# photon_v1_0_0.net
KiCad netlist of a schematic drawn in EAGLE
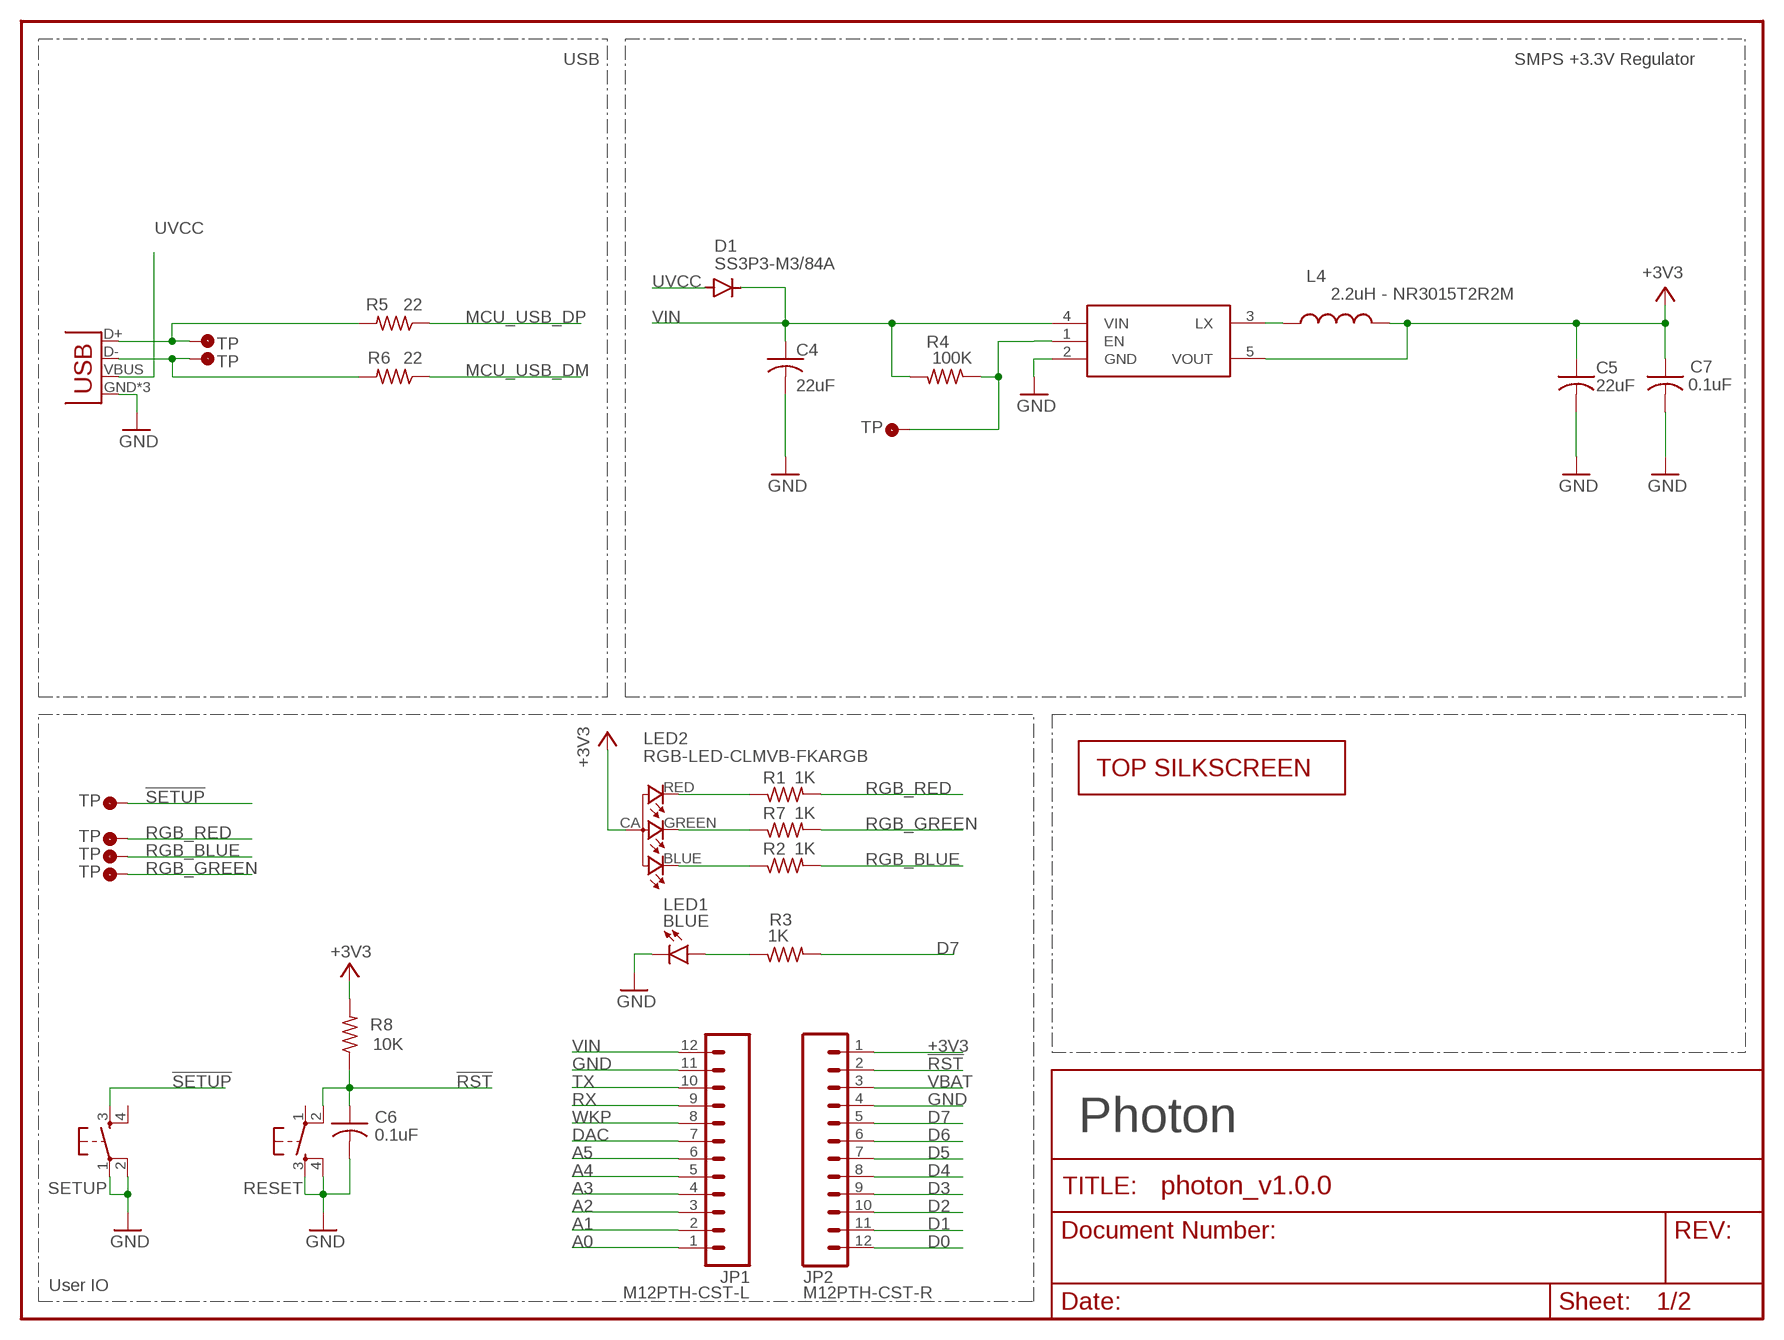
[diagram p0: schematic, sheet 1]
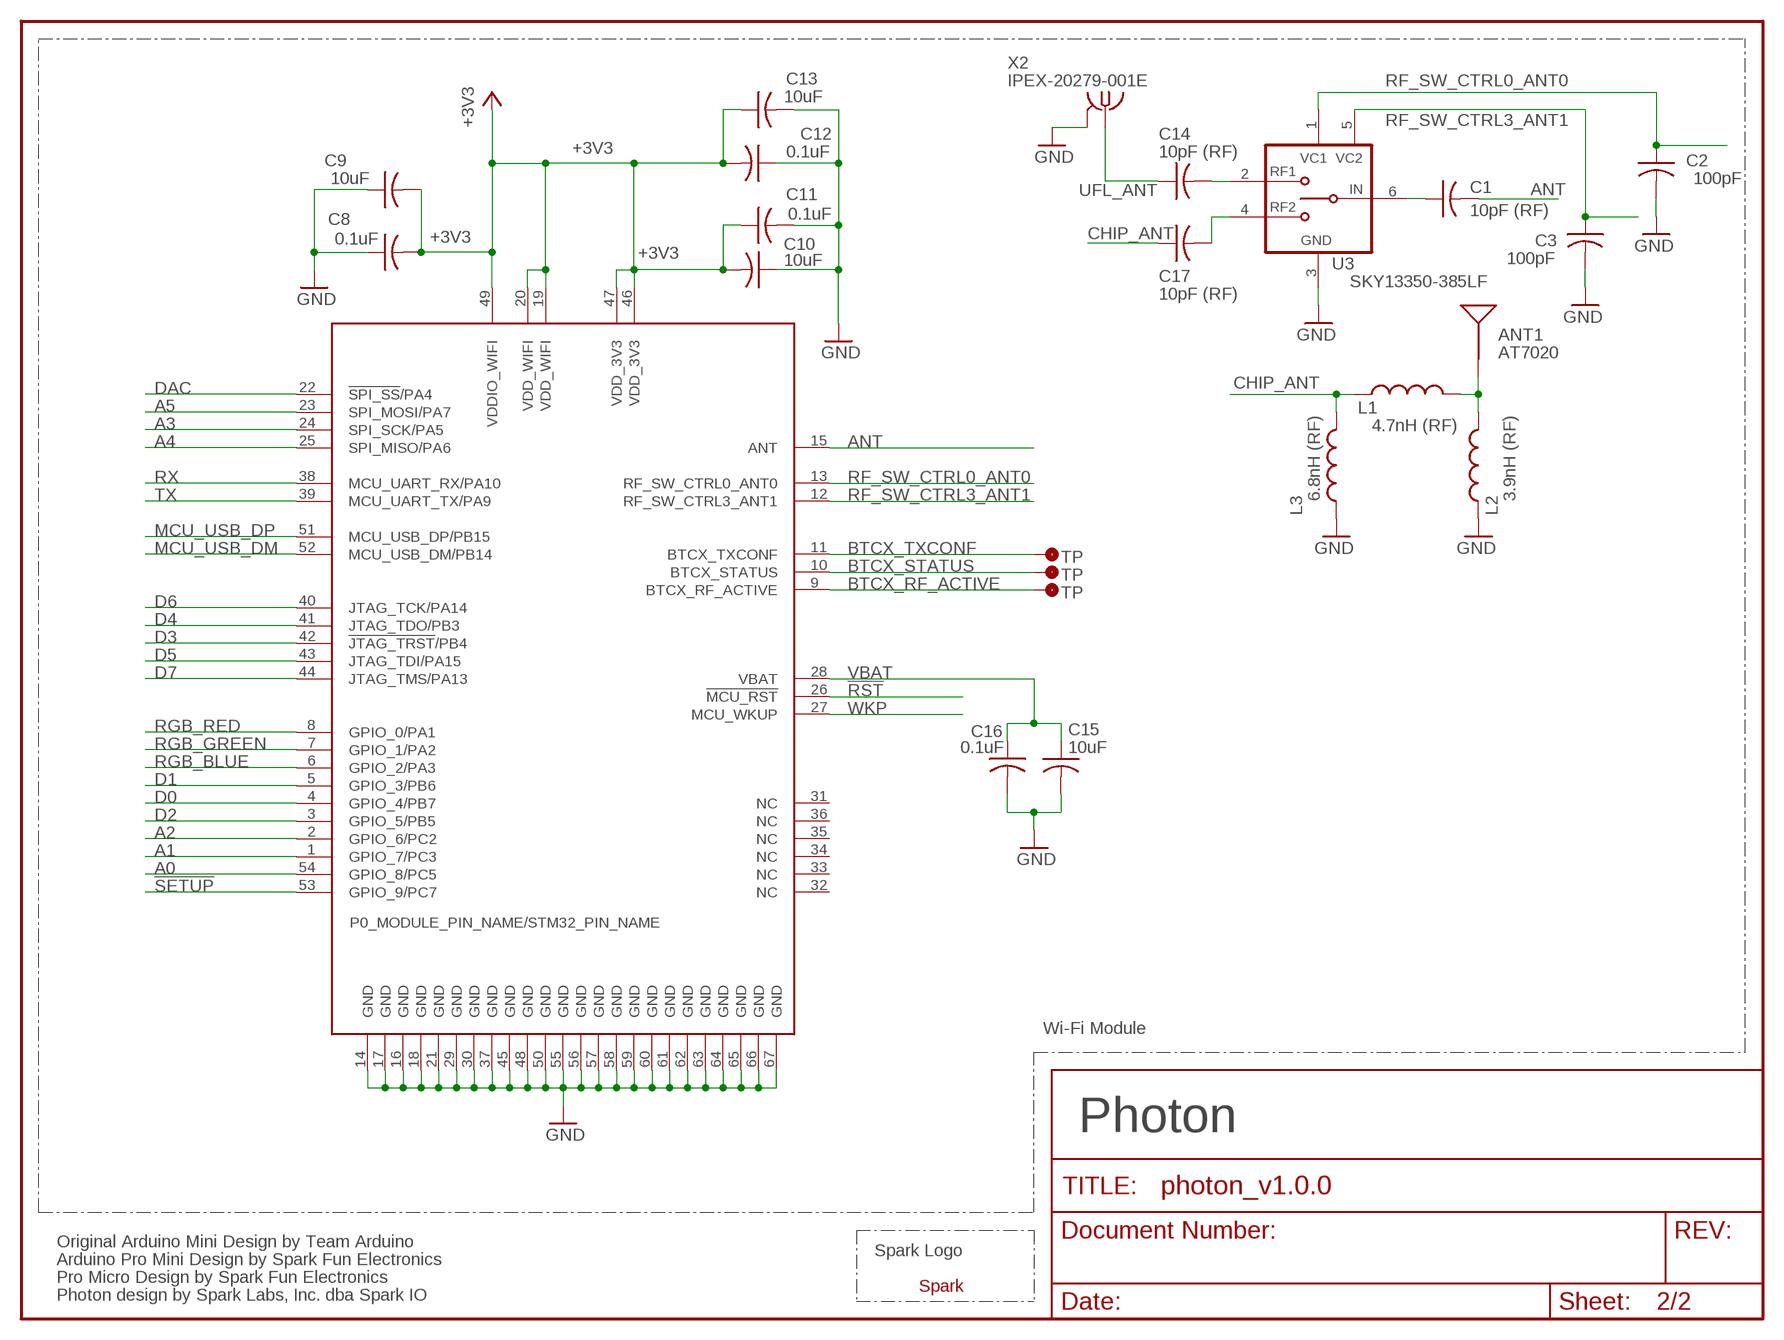
[diagram p1: schematic, sheet 2]

(export (version "E")
  (design (tool "Eeschema 10.0.6"))
  (components
    (comp (ref "ANT1")
      (value "AT7020")
      (footprint "eagle-import:AT7020")
      (libsource (lib "eagle-import") (part "AT7020"))
    )
    (comp (ref "C1")
      (value "10pF (RF)")
      (footprint "eagle-import:C0201_B")
      (libsource (lib "eagle-import") (part "C-US0201"))
    )
    (comp (ref "C2")
      (value "100pF")
      (footprint "eagle-import:C0402_B")
      (libsource (lib "eagle-import") (part "C-US"))
    )
    (comp (ref "C3")
      (value "100pF")
      (footprint "eagle-import:C0402_B")
      (libsource (lib "eagle-import") (part "C-US"))
    )
    (comp (ref "C8")
      (value "0.1uF")
      (footprint "eagle-import:C0402_B")
      (libsource (lib "eagle-import") (part "C-US"))
    )
    (comp (ref "C9")
      (value "10uF")
      (footprint "eagle-import:C0603_B")
      (libsource (lib "eagle-import") (part "C-US0603"))
    )
    (comp (ref "C10")
      (value "10uF")
      (footprint "eagle-import:C0603_B")
      (libsource (lib "eagle-import") (part "C-US0603"))
    )
    (comp (ref "C11")
      (value "0.1uF")
      (footprint "eagle-import:C0402_B")
      (libsource (lib "eagle-import") (part "C-US"))
    )
    (comp (ref "C12")
      (value "0.1uF")
      (footprint "eagle-import:C0402_B")
      (libsource (lib "eagle-import") (part "C-US"))
    )
    (comp (ref "C13")
      (value "10uF")
      (footprint "eagle-import:C0603_B")
      (libsource (lib "eagle-import") (part "C-US0603"))
    )
    (comp (ref "C14")
      (value "10pF (RF)")
      (footprint "eagle-import:C0201_B")
      (libsource (lib "eagle-import") (part "C-US0201"))
    )
    (comp (ref "C15")
      (value "10uF")
      (footprint "eagle-import:C0603_B")
      (libsource (lib "eagle-import") (part "C-US0603"))
    )
    (comp (ref "C16")
      (value "0.1uF")
      (footprint "eagle-import:C0402_B")
      (libsource (lib "eagle-import") (part "C-US"))
    )
    (comp (ref "C17")
      (value "10pF (RF)")
      (footprint "eagle-import:C0201_B")
      (libsource (lib "eagle-import") (part "C-US0201"))
    )
    (comp (ref "L1")
      (value "4.7nH (RF)")
      (footprint "eagle-import:L0402_B")
      (libsource (lib "eagle-import") (part "INDUCTOR"))
    )
    (comp (ref "L2")
      (value "3.9nH (RF)")
      (footprint "eagle-import:L0402_B")
      (libsource (lib "eagle-import") (part "INDUCTOR"))
    )
    (comp (ref "L3")
      (value "6.8nH (RF)")
      (footprint "eagle-import:L0402_B")
      (libsource (lib "eagle-import") (part "INDUCTOR"))
    )
    (comp (ref "U$2")
      (value "SPARK_LOGO2")
      (footprint "eagle-import:SPARK_LOGO2")
      (libsource (lib "eagle-import") (part "SPARK_LOGO2"))
    )
    (comp (ref "U$8")
      (value "TP1")
      (footprint "eagle-import:TP35_BOT")
      (libsource (lib "eagle-import") (part "TP1"))
    )
    (comp (ref "U$9")
      (value "TP1")
      (footprint "eagle-import:TP35_BOT")
      (libsource (lib "eagle-import") (part "TP1"))
    )
    (comp (ref "U$10")
      (value "TP1")
      (footprint "eagle-import:TP35_BOT")
      (libsource (lib "eagle-import") (part "TP1"))
    )
    (comp (ref "U1")
      (value "WM-N-BM-09")
      (footprint "eagle-import:WM-N-BM-09")
      (libsource (lib "eagle-import") (part "WM-N-BM-09"))
    )
    (comp (ref "U3")
      (value "SKY13350-385LF")
      (footprint "eagle-import:XFDFN-6")
      (libsource (lib "eagle-import") (part "SKY13350-385LF"))
    )
    (comp (ref "X2")
      (value "IPEX-20279-001E")
      (footprint "eagle-import:IPEX-20279-001E")
      (libsource (lib "eagle-import") (part "IPEX-20279-001E"))
    )
    (comp (ref "C4")
      (value "22uF")
      (footprint "eagle-import:C0603_B")
      (libsource (lib "eagle-import") (part "C-US0603"))
    )
    (comp (ref "C5")
      (value "22uF")
      (footprint "eagle-import:C0603_B")
      (libsource (lib "eagle-import") (part "C-US0603"))
    )
    (comp (ref "C6")
      (value "0.1uF")
      (footprint "eagle-import:C0402_B")
      (libsource (lib "eagle-import") (part "C-US"))
    )
    (comp (ref "C7")
      (value "0.1uF")
      (footprint "eagle-import:C0402_B")
      (libsource (lib "eagle-import") (part "C-US"))
    )
    (comp (ref "D1")
      (value "SS3P3-M3/84A")
      (footprint "eagle-import:DIODE-DO-220AA(SMP)")
      (libsource (lib "eagle-import") (part "DIODE"))
    )
    (comp (ref "JP1")
      (value "M12PTH-CST-L")
      (footprint "eagle-import:1X12-CASTELLATED")
      (libsource (lib "eagle-import") (part "M12PTH-CST-L"))
    )
    (comp (ref "JP2")
      (value "M12PTH-CST-R")
      (footprint "eagle-import:1X12-CASTELLATED")
      (libsource (lib "eagle-import") (part "M12PTH-CST-R"))
    )
    (comp (ref "L4")
      (value "2.2uH - NR3015T2R2M")
      (footprint "eagle-import:INDUCTOR-NR3015")
      (libsource (lib "eagle-import") (part "INDUCTORB"))
    )
    (comp (ref "LED2")
      (value "RGB-LED-CLMVB-FKARGB")
      (footprint "eagle-import:PLCC4-2MM-RGB")
      (libsource (lib "eagle-import") (part "RGB-LED-CLMVB-FKARGB"))
    )
    (comp (ref "LED_USR")
      (value "BLUE")
      (footprint "eagle-import:LED-0603-NO-SS")
      (libsource (lib "eagle-import") (part "LED-0603-NO-SS"))
    )
    (comp (ref "R1")
      (value "1K")
      (footprint "eagle-import:R0402_B")
      (libsource (lib "eagle-import") (part "R-US_"))
    )
    (comp (ref "R2")
      (value "1K")
      (footprint "eagle-import:R0402_B")
      (libsource (lib "eagle-import") (part "R-US_"))
    )
    (comp (ref "R3")
      (value "1K")
      (footprint "eagle-import:R0402_B")
      (libsource (lib "eagle-import") (part "R-US_"))
    )
    (comp (ref "R4")
      (value "100K")
      (footprint "eagle-import:R0402_B")
      (libsource (lib "eagle-import") (part "R-US_"))
    )
    (comp (ref "R5")
      (value "22")
      (footprint "eagle-import:R0402_B")
      (libsource (lib "eagle-import") (part "R-US_"))
    )
    (comp (ref "R6")
      (value "22")
      (footprint "eagle-import:R0402_B")
      (libsource (lib "eagle-import") (part "R-US_"))
    )
    (comp (ref "R7")
      (value "1K")
      (footprint "eagle-import:R0402_B")
      (libsource (lib "eagle-import") (part "R-US_"))
    )
    (comp (ref "R8")
      (value "10K")
      (footprint "eagle-import:R0402_B")
      (libsource (lib "eagle-import") (part "R-US_"))
    )
    (comp (ref "RESET")
      (value "KMR211GLFS")
      (footprint "eagle-import:TACTILE_SWITCH_SMD")
      (libsource (lib "eagle-import") (part "TAC_SWITCHSMD"))
    )
    (comp (ref "SETUP")
      (value "KMR211GLFS")
      (footprint "eagle-import:TACTILE_SWITCH_SMD")
      (libsource (lib "eagle-import") (part "TAC_SWITCHSMD"))
    )
    (comp (ref "U$1")
      (value "PHOTON-TOP-SS2")
      (footprint "eagle-import:PHOTON-TOP-SS-2")
      (libsource (lib "eagle-import") (part "PHOTON-TOP-SS2"))
    )
    (comp (ref "U$3")
      (value "TP3")
      (footprint "eagle-import:TP60_BOT")
      (libsource (lib "eagle-import") (part "TP3"))
    )
    (comp (ref "U$5")
      (value "TP1")
      (footprint "eagle-import:TP35_BOT")
      (libsource (lib "eagle-import") (part "TP1"))
    )
    (comp (ref "U$6")
      (value "TP1")
      (footprint "eagle-import:TP35_BOT")
      (libsource (lib "eagle-import") (part "TP1"))
    )
    (comp (ref "U$7")
      (value "TP1")
      (footprint "eagle-import:TP35_BOT")
      (libsource (lib "eagle-import") (part "TP1"))
    )
    (comp (ref "U$11")
      (value "R8008-33")
      (footprint "eagle-import:SOT23-5")
      (libsource (lib "eagle-import") (part "R8008-33"))
    )
    (comp (ref "U$12")
      (value "TP3")
      (footprint "eagle-import:TP60_BOT")
      (libsource (lib "eagle-import") (part "TP3"))
    )
    (comp (ref "U$13")
      (value "TP3")
      (footprint "eagle-import:TP60_BOT")
      (libsource (lib "eagle-import") (part "TP3"))
    )
    (comp (ref "U$14")
      (value "TP3")
      (footprint "eagle-import:TP60_BOT")
      (libsource (lib "eagle-import") (part "TP3"))
    )
    (comp (ref "X1")
      (value "USB-MICROB")
      (footprint "eagle-import:USB-MICROB-SLOT-HOLE")
      (libsource (lib "eagle-import") (part "USBUSB-MICROB-SLOT-HOLE"))
    )
  )
  (nets
    (net (code "1") (name "+3V3") (class "Default")
      (node (ref "C10") (pin "2") (pinfunction "2_2") (pintype "passive"))
      (node (ref "C11") (pin "1") (pinfunction "1_1") (pintype "passive"))
      (node (ref "C12") (pin "2") (pinfunction "2_2") (pintype "passive"))
      (node (ref "C13") (pin "1") (pinfunction "1_1") (pintype "passive"))
      (node (ref "C5") (pin "1") (pinfunction "1_1") (pintype "passive"))
      (node (ref "C7") (pin "1") (pinfunction "1_1") (pintype "passive"))
      (node (ref "C8") (pin "2") (pinfunction "2_2") (pintype "passive"))
      (node (ref "C9") (pin "2") (pinfunction "2_2") (pintype "passive"))
      (node (ref "JP2") (pin "1") (pinfunction "1_1") (pintype "passive"))
      (node (ref "L4") (pin "2") (pinfunction "2_2") (pintype "passive"))
      (node (ref "LED2") (pin "CA") (pinfunction "1_CA") (pintype "passive"))
      (node (ref "R8") (pin "2") (pinfunction "2_2") (pintype "passive"))
      (node (ref "U$11") (pin "5") (pinfunction "VOUT_5") (pintype "bidirectional"))
      (node (ref "U1") (pin "19") (pinfunction "VDD_WIFI_19") (pintype "bidirectional"))
      (node (ref "U1") (pin "20") (pinfunction "VDD_WIFI_20") (pintype "bidirectional"))
      (node (ref "U1") (pin "46") (pinfunction "VDD_3V3_46") (pintype "bidirectional"))
      (node (ref "U1") (pin "47") (pinfunction "VDD_3V3_47") (pintype "bidirectional"))
      (node (ref "U1") (pin "49") (pinfunction "VDDIO_WIFI_49") (pintype "bidirectional"))
    )
    (net (code "2") (name "A0") (class "Default")
      (node (ref "JP1") (pin "1") (pinfunction "12_1") (pintype "passive"))
      (node (ref "U1") (pin "54") (pinfunction "GPIO_8/PC5_54") (pintype "bidirectional"))
    )
    (net (code "3") (name "A1") (class "Default")
      (node (ref "JP1") (pin "2") (pinfunction "11_2") (pintype "passive"))
      (node (ref "U1") (pin "1") (pinfunction "GPIO_7/PC3_1") (pintype "bidirectional"))
    )
    (net (code "4") (name "A2") (class "Default")
      (node (ref "JP1") (pin "3") (pinfunction "10_3") (pintype "passive"))
      (node (ref "U1") (pin "2") (pinfunction "GPIO_6/PC2_2") (pintype "bidirectional"))
    )
    (net (code "5") (name "A3") (class "Default")
      (node (ref "JP1") (pin "4") (pinfunction "9_4") (pintype "passive"))
      (node (ref "U1") (pin "24") (pinfunction "SPI_SCK/PA5_24") (pintype "bidirectional"))
    )
    (net (code "6") (name "A4") (class "Default")
      (node (ref "JP1") (pin "5") (pinfunction "8_5") (pintype "passive"))
      (node (ref "U1") (pin "25") (pinfunction "SPI_MISO/PA6_25") (pintype "bidirectional"))
    )
    (net (code "7") (name "A5") (class "Default")
      (node (ref "JP1") (pin "6") (pinfunction "7_6") (pintype "passive"))
      (node (ref "U1") (pin "23") (pinfunction "SPI_MOSI/PA7_23") (pintype "bidirectional"))
    )
    (net (code "8") (name "ANT") (class "Default")
      (node (ref "C1") (pin "2") (pinfunction "2_2") (pintype "passive"))
      (node (ref "U1") (pin "15") (pinfunction "ANT_15") (pintype "bidirectional"))
    )
    (net (code "9") (name "BTCX_RF_ACTIVE") (class "Default")
      (node (ref "U$10") (pin "P$1") (pinfunction "TP_P$1") (pintype "bidirectional"))
      (node (ref "U1") (pin "9") (pinfunction "BTCX_RF_ACTIVE_9") (pintype "bidirectional"))
    )
    (net (code "10") (name "BTCX_STATUS") (class "Default")
      (node (ref "U$9") (pin "P$1") (pinfunction "TP_P$1") (pintype "bidirectional"))
      (node (ref "U1") (pin "10") (pinfunction "BTCX_STATUS_10") (pintype "bidirectional"))
    )
    (net (code "11") (name "BTCX_TXCONF") (class "Default")
      (node (ref "U$8") (pin "P$1") (pinfunction "TP_P$1") (pintype "bidirectional"))
      (node (ref "U1") (pin "11") (pinfunction "BTCX_TXCONF_11") (pintype "bidirectional"))
    )
    (net (code "12") (name "CHIP_ANT") (class "Default")
      (node (ref "C17") (pin "1") (pinfunction "1_1") (pintype "passive"))
      (node (ref "L1") (pin "1") (pinfunction "1_1") (pintype "passive"))
      (node (ref "L3") (pin "2") (pinfunction "2_2") (pintype "passive"))
    )
    (net (code "13") (name "D0") (class "Default")
      (node (ref "JP2") (pin "12") (pinfunction "12_12") (pintype "passive"))
      (node (ref "U1") (pin "4") (pinfunction "GPIO_4/PB7_4") (pintype "bidirectional"))
    )
    (net (code "14") (name "D1") (class "Default")
      (node (ref "JP2") (pin "11") (pinfunction "11_11") (pintype "passive"))
      (node (ref "U1") (pin "5") (pinfunction "GPIO_3/PB6_5") (pintype "bidirectional"))
    )
    (net (code "15") (name "D2") (class "Default")
      (node (ref "JP2") (pin "10") (pinfunction "10_10") (pintype "passive"))
      (node (ref "U1") (pin "3") (pinfunction "GPIO_5/PB5_3") (pintype "bidirectional"))
    )
    (net (code "16") (name "D3") (class "Default")
      (node (ref "JP2") (pin "9") (pinfunction "9_9") (pintype "passive"))
      (node (ref "U1") (pin "42") (pinfunction "~{JTAG_TRST}/PB4_42") (pintype "bidirectional"))
    )
    (net (code "17") (name "D4") (class "Default")
      (node (ref "JP2") (pin "8") (pinfunction "8_8") (pintype "passive"))
      (node (ref "U1") (pin "41") (pinfunction "JTAG_TDO/PB3_41") (pintype "bidirectional"))
    )
    (net (code "18") (name "D5") (class "Default")
      (node (ref "JP2") (pin "7") (pinfunction "7_7") (pintype "passive"))
      (node (ref "U1") (pin "43") (pinfunction "JTAG_TDI/PA15_43") (pintype "bidirectional"))
    )
    (net (code "19") (name "D6") (class "Default")
      (node (ref "JP2") (pin "6") (pinfunction "6_6") (pintype "passive"))
      (node (ref "U1") (pin "40") (pinfunction "JTAG_TCK/PA14_40") (pintype "bidirectional"))
    )
    (net (code "20") (name "D7") (class "Default")
      (node (ref "JP2") (pin "5") (pinfunction "5_5") (pintype "passive"))
      (node (ref "R3") (pin "2") (pinfunction "2_2") (pintype "passive"))
      (node (ref "U1") (pin "44") (pinfunction "JTAG_TMS/PA13_44") (pintype "bidirectional"))
    )
    (net (code "21") (name "DAC") (class "Default")
      (node (ref "JP1") (pin "7") (pinfunction "6_7") (pintype "passive"))
      (node (ref "U1") (pin "22") (pinfunction "~{SPI_SS}/PA4_22") (pintype "bidirectional"))
    )
    (net (code "22") (name "GND") (class "Default")
      (node (ref "C10") (pin "1") (pinfunction "1_1") (pintype "passive"))
      (node (ref "C11") (pin "2") (pinfunction "2_2") (pintype "passive"))
      (node (ref "C12") (pin "1") (pinfunction "1_1") (pintype "passive"))
      (node (ref "C13") (pin "2") (pinfunction "2_2") (pintype "passive"))
      (node (ref "C15") (pin "2") (pinfunction "2_2") (pintype "passive"))
      (node (ref "C16") (pin "2") (pinfunction "2_2") (pintype "passive"))
      (node (ref "C2") (pin "2") (pinfunction "2_2") (pintype "passive"))
      (node (ref "C3") (pin "2") (pinfunction "2_2") (pintype "passive"))
      (node (ref "C4") (pin "2") (pinfunction "2_2") (pintype "passive"))
      (node (ref "C5") (pin "2") (pinfunction "2_2") (pintype "passive"))
      (node (ref "C6") (pin "2") (pinfunction "2_2") (pintype "passive"))
      (node (ref "C7") (pin "2") (pinfunction "2_2") (pintype "passive"))
      (node (ref "C8") (pin "1") (pinfunction "1_1") (pintype "passive"))
      (node (ref "C9") (pin "1") (pinfunction "1_1") (pintype "passive"))
      (node (ref "JP1") (pin "11") (pinfunction "2_11") (pintype "passive"))
      (node (ref "JP2") (pin "4") (pinfunction "4_4") (pintype "passive"))
      (node (ref "L2") (pin "1") (pinfunction "1_1") (pintype "passive"))
      (node (ref "L3") (pin "1") (pinfunction "1_1") (pintype "passive"))
      (node (ref "LED_USR") (pin "C1") (pinfunction "C_C1") (pintype "passive"))
      (node (ref "RESET") (pin "3") (pinfunction "3_3") (pintype "passive"))
      (node (ref "RESET") (pin "4") (pinfunction "4_4") (pintype "passive"))
      (node (ref "SETUP") (pin "1") (pinfunction "1_1") (pintype "passive"))
      (node (ref "SETUP") (pin "2") (pinfunction "2_2") (pintype "passive"))
      (node (ref "U$11") (pin "2") (pinfunction "GND_2") (pintype "bidirectional"))
      (node (ref "U1") (pin "14") (pinfunction "GND_14") (pintype "bidirectional"))
      (node (ref "U1") (pin "16") (pinfunction "GND_16") (pintype "bidirectional"))
      (node (ref "U1") (pin "17") (pinfunction "GND_17") (pintype "bidirectional"))
      (node (ref "U1") (pin "18") (pinfunction "GND_18") (pintype "bidirectional"))
      (node (ref "U1") (pin "21") (pinfunction "GND_21") (pintype "bidirectional"))
      (node (ref "U1") (pin "29") (pinfunction "GND_29") (pintype "bidirectional"))
      (node (ref "U1") (pin "30") (pinfunction "GND_30") (pintype "bidirectional"))
      (node (ref "U1") (pin "37") (pinfunction "GND_37") (pintype "bidirectional"))
      (node (ref "U1") (pin "45") (pinfunction "GND_45") (pintype "bidirectional"))
      (node (ref "U1") (pin "48") (pinfunction "GND_48") (pintype "bidirectional"))
      (node (ref "U1") (pin "50") (pinfunction "GND_50") (pintype "bidirectional"))
      (node (ref "U1") (pin "55") (pinfunction "GND_55") (pintype "bidirectional"))
      (node (ref "U1") (pin "56") (pinfunction "GND_56") (pintype "bidirectional"))
      (node (ref "U1") (pin "57") (pinfunction "GND_57") (pintype "bidirectional"))
      (node (ref "U1") (pin "58") (pinfunction "GND_58") (pintype "bidirectional"))
      (node (ref "U1") (pin "59") (pinfunction "GND_59") (pintype "bidirectional"))
      (node (ref "U1") (pin "60") (pinfunction "GND_60") (pintype "bidirectional"))
      (node (ref "U1") (pin "61") (pinfunction "GND_61") (pintype "bidirectional"))
      (node (ref "U1") (pin "62") (pinfunction "GND_62") (pintype "bidirectional"))
      (node (ref "U1") (pin "63") (pinfunction "GND_63") (pintype "bidirectional"))
      (node (ref "U1") (pin "64") (pinfunction "GND_64") (pintype "bidirectional"))
      (node (ref "U1") (pin "65") (pinfunction "GND_65") (pintype "bidirectional"))
      (node (ref "U1") (pin "66") (pinfunction "GND_66") (pintype "bidirectional"))
      (node (ref "U1") (pin "67") (pinfunction "GND_67") (pintype "bidirectional"))
      (node (ref "U3") (pin "3") (pinfunction "GND_3") (pintype "power_in"))
      (node (ref "X1") (pin "GND") (pinfunction "GND_GND") (pintype "bidirectional"))
      (node (ref "X1") (pin "MT1") (pinfunction "GND_MT1") (pintype "bidirectional"))
      (node (ref "X1") (pin "MT2") (pinfunction "GND_MT2") (pintype "bidirectional"))
      (node (ref "X2") (pin "2@1") (pinfunction "GND_2@1") (pintype "passive"))
      (node (ref "X2") (pin "2@2") (pinfunction "GND_2@2") (pintype "passive"))
    )
    (net (code "23") (name "LED1") (class "Default")
      (node (ref "LED_USR") (pin "A1") (pinfunction "A_A1") (pintype "passive"))
      (node (ref "R3") (pin "1") (pinfunction "1_1") (pintype "passive"))
    )
    (net (code "24") (name "MCU_USB_DM") (class "Default")
      (node (ref "R6") (pin "1") (pinfunction "1_1") (pintype "passive"))
      (node (ref "U1") (pin "52") (pinfunction "MCU_USB_DM/PB14_52") (pintype "bidirectional"))
    )
    (net (code "25") (name "MCU_USB_DP") (class "Default")
      (node (ref "R5") (pin "1") (pinfunction "1_1") (pintype "passive"))
      (node (ref "U1") (pin "51") (pinfunction "MCU_USB_DP/PB15_51") (pintype "bidirectional"))
    )
    (net (code "26") (name "Net-(ANT1-SIGNAL)") (class "Default")
      (node (ref "ANT1") (pin "1") (pinfunction "SIGNAL_1") (pintype "bidirectional"))
      (node (ref "L1") (pin "2") (pinfunction "2_2") (pintype "passive"))
      (node (ref "L2") (pin "2") (pinfunction "2_2") (pintype "passive"))
    )
    (net (code "27") (name "Net-(LED2-2)") (class "Default")
      (node (ref "LED2") (pin "BLUE") (pinfunction "2_BLUE") (pintype "passive"))
      (node (ref "R2") (pin "1") (pinfunction "1_1") (pintype "passive"))
    )
    (net (code "28") (name "Net-(LED2-3)") (class "Default")
      (node (ref "LED2") (pin "GREEN") (pinfunction "3_GREEN") (pintype "passive"))
      (node (ref "R7") (pin "1") (pinfunction "1_1") (pintype "passive"))
    )
    (net (code "29") (name "Net-(LED2-4)") (class "Default")
      (node (ref "LED2") (pin "RED") (pinfunction "4_RED") (pintype "passive"))
      (node (ref "R1") (pin "1") (pinfunction "1_1") (pintype "passive"))
    )
    (net (code "30") (name "Net-(U$11-EN)") (class "Default")
      (node (ref "R4") (pin "1") (pinfunction "1_1") (pintype "passive"))
      (node (ref "U$11") (pin "1") (pinfunction "EN_1") (pintype "bidirectional"))
      (node (ref "U$12") (pin "P$1") (pinfunction "TP_P$1") (pintype "bidirectional"))
    )
    (net (code "31") (name "Net-(U$11-LX)") (class "Default")
      (node (ref "L4") (pin "1") (pinfunction "1_1") (pintype "passive"))
      (node (ref "U$11") (pin "3") (pinfunction "LX_3") (pintype "bidirectional"))
    )
    (net (code "32") (name "Net-(U$13-TP)") (class "Default")
      (node (ref "R5") (pin "2") (pinfunction "2_2") (pintype "passive"))
      (node (ref "U$13") (pin "P$1") (pinfunction "TP_P$1") (pintype "bidirectional"))
      (node (ref "X1") (pin "D+") (pinfunction "D+_D+") (pintype "bidirectional"))
    )
    (net (code "33") (name "Net-(U$14-TP)") (class "Default")
      (node (ref "R6") (pin "2") (pinfunction "2_2") (pintype "passive"))
      (node (ref "U$14") (pin "P$1") (pinfunction "TP_P$1") (pintype "bidirectional"))
      (node (ref "X1") (pin "D-") (pinfunction "D-_D-") (pintype "bidirectional"))
    )
    (net (code "34") (name "Net-(U3B-IN)") (class "Default")
      (node (ref "C1") (pin "1") (pinfunction "1_1") (pintype "passive"))
      (node (ref "U3") (pin "6") (pinfunction "IN_6") (pintype "bidirectional"))
    )
    (net (code "35") (name "Net-(U3B-RF1)") (class "Default")
      (node (ref "C14") (pin "2") (pinfunction "2_2") (pintype "passive"))
      (node (ref "U3") (pin "2") (pinfunction "RF1_2") (pintype "bidirectional"))
    )
    (net (code "36") (name "Net-(U3B-RF2)") (class "Default")
      (node (ref "C17") (pin "2") (pinfunction "2_2") (pintype "passive"))
      (node (ref "U3") (pin "4") (pinfunction "RF2_4") (pintype "bidirectional"))
    )
    (net (code "37") (name "RF_SW_CTRL0_ANT0") (class "Default")
      (node (ref "C2") (pin "1") (pinfunction "1_1") (pintype "passive"))
      (node (ref "U1") (pin "13") (pinfunction "RF_SW_CTRL0_ANT0_13") (pintype "bidirectional"))
      (node (ref "U3") (pin "1") (pinfunction "VC1_1") (pintype "input"))
    )
    (net (code "38") (name "RF_SW_CTRL3_ANT1") (class "Default")
      (node (ref "C3") (pin "1") (pinfunction "1_1") (pintype "passive"))
      (node (ref "U1") (pin "12") (pinfunction "RF_SW_CTRL3_ANT1_12") (pintype "bidirectional"))
      (node (ref "U3") (pin "5") (pinfunction "VC2_5") (pintype "input"))
    )
    (net (code "39") (name "RGB_BLUE") (class "Default")
      (node (ref "R2") (pin "2") (pinfunction "2_2") (pintype "passive"))
      (node (ref "U$6") (pin "P$1") (pinfunction "TP_P$1") (pintype "bidirectional"))
      (node (ref "U1") (pin "6") (pinfunction "GPIO_2/PA3_6") (pintype "bidirectional"))
    )
    (net (code "40") (name "RGB_GREEN") (class "Default")
      (node (ref "R7") (pin "2") (pinfunction "2_2") (pintype "passive"))
      (node (ref "U$7") (pin "P$1") (pinfunction "TP_P$1") (pintype "bidirectional"))
      (node (ref "U1") (pin "7") (pinfunction "GPIO_1/PA2_7") (pintype "bidirectional"))
    )
    (net (code "41") (name "RGB_RED") (class "Default")
      (node (ref "R1") (pin "2") (pinfunction "2_2") (pintype "passive"))
      (node (ref "U$5") (pin "P$1") (pinfunction "TP_P$1") (pintype "bidirectional"))
      (node (ref "U1") (pin "8") (pinfunction "GPIO_0/PA1_8") (pintype "bidirectional"))
    )
    (net (code "42") (name "RX") (class "Default")
      (node (ref "JP1") (pin "9") (pinfunction "4_9") (pintype "passive"))
      (node (ref "U1") (pin "38") (pinfunction "MCU_UART_RX/PA10_38") (pintype "bidirectional"))
    )
    (net (code "43") (name "TX") (class "Default")
      (node (ref "JP1") (pin "10") (pinfunction "3_10") (pintype "passive"))
      (node (ref "U1") (pin "39") (pinfunction "MCU_UART_TX/PA9_39") (pintype "bidirectional"))
    )
    (net (code "44") (name "UFL_ANT") (class "Default")
      (node (ref "C14") (pin "1") (pinfunction "1_1") (pintype "passive"))
      (node (ref "X2") (pin "1") (pinfunction "1_1") (pintype "passive"))
    )
    (net (code "45") (name "UVCC") (class "Default")
      (node (ref "D1") (pin "ANODE") (pinfunction "ANODE_ANODE") (pintype "bidirectional"))
      (node (ref "X1") (pin "VBUS") (pinfunction "VBUS_VBUS") (pintype "bidirectional"))
    )
    (net (code "46") (name "VBAT") (class "Default")
      (node (ref "C15") (pin "1") (pinfunction "1_1") (pintype "passive"))
      (node (ref "C16") (pin "1") (pinfunction "1_1") (pintype "passive"))
      (node (ref "JP2") (pin "3") (pinfunction "3_3") (pintype "passive"))
      (node (ref "U1") (pin "28") (pinfunction "VBAT_28") (pintype "bidirectional"))
    )
    (net (code "47") (name "VIN") (class "Default")
      (node (ref "C4") (pin "1") (pinfunction "1_1") (pintype "passive"))
      (node (ref "D1") (pin "CATHODE") (pinfunction "CATHODE_CATHODE") (pintype "bidirectional"))
      (node (ref "JP1") (pin "12") (pinfunction "1_12") (pintype "passive"))
      (node (ref "R4") (pin "2") (pinfunction "2_2") (pintype "passive"))
      (node (ref "U$11") (pin "4") (pinfunction "VIN_4") (pintype "bidirectional"))
    )
    (net (code "48") (name "WKP") (class "Default")
      (node (ref "JP1") (pin "8") (pinfunction "5_8") (pintype "passive"))
      (node (ref "U1") (pin "27") (pinfunction "MCU_WKUP_27") (pintype "bidirectional"))
    )
    (net (code "49") (name "unconnected-(RESET-Pad1)") (class "Default")
      (node (ref "RESET") (pin "1") (pinfunction "1_1") (pintype "passive"))
    )
    (net (code "50") (name "unconnected-(SETUP-Pad4)") (class "Default")
      (node (ref "SETUP") (pin "4") (pinfunction "4_4") (pintype "passive"))
    )
    (net (code "51") (name "unconnected-(U1-NC-Pad31)") (class "Default")
      (node (ref "U1") (pin "31") (pinfunction "NC_31") (pintype "bidirectional"))
    )
    (net (code "52") (name "unconnected-(U1-NC-Pad32)") (class "Default")
      (node (ref "U1") (pin "32") (pinfunction "NC_32") (pintype "bidirectional"))
    )
    (net (code "53") (name "unconnected-(U1-NC-Pad33)") (class "Default")
      (node (ref "U1") (pin "33") (pinfunction "NC_33") (pintype "bidirectional"))
    )
    (net (code "54") (name "unconnected-(U1-NC-Pad34)") (class "Default")
      (node (ref "U1") (pin "34") (pinfunction "NC_34") (pintype "bidirectional"))
    )
    (net (code "55") (name "unconnected-(U1-NC-Pad35)") (class "Default")
      (node (ref "U1") (pin "35") (pinfunction "NC_35") (pintype "bidirectional"))
    )
    (net (code "56") (name "unconnected-(U1-NC-Pad36)") (class "Default")
      (node (ref "U1") (pin "36") (pinfunction "NC_36") (pintype "bidirectional"))
    )
    (net (code "57") (name "~{RST}") (class "Default")
      (node (ref "C6") (pin "1") (pinfunction "1_1") (pintype "passive"))
      (node (ref "JP2") (pin "2") (pinfunction "2_2") (pintype "passive"))
      (node (ref "R8") (pin "1") (pinfunction "1_1") (pintype "passive"))
      (node (ref "RESET") (pin "2") (pinfunction "2_2") (pintype "passive"))
      (node (ref "U1") (pin "26") (pinfunction "~{MCU_RST}_26") (pintype "bidirectional"))
    )
    (net (code "58") (name "~{SETUP}") (class "Default")
      (node (ref "SETUP") (pin "3") (pinfunction "3_3") (pintype "passive"))
      (node (ref "U$3") (pin "P$1") (pinfunction "TP_P$1") (pintype "bidirectional"))
      (node (ref "U1") (pin "53") (pinfunction "GPIO_9/PC7_53") (pintype "bidirectional"))
    )
  )
)
